# DC_DC_5V.net
KiCad netlist of a schematic drawn in Altium Designer
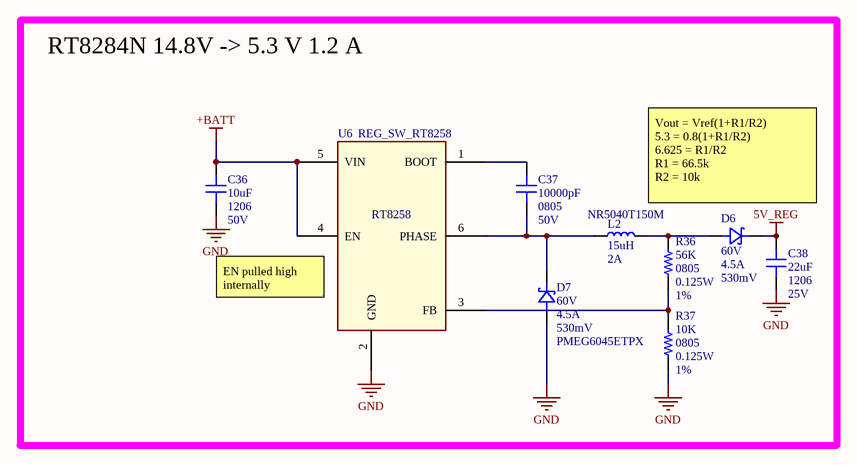
[diagram p0: DC_DC_5V.SchDoc]

(export (version "E")
  (design (tool "Eeschema 10.0.6"))
  (components
    (comp (ref "C36")
      (value "10uF")
      (footprint "CAP_1206")
      (description "CAP CER 10uF 50V 1206")
      (fields
        (field (name "PART NUMBER") "GRT31CR61H106ME01L‎")
        (field (name "PACKAGE") "1206")
        (field (name "VOLTAGE") "50V")
        (field (name "Comment") "CAP_GRT31CR61H106ME01L‎")
      )
      (libsource (lib "SecureBot") (part "CAP_GRT31CR61H106ME01L‎"))
    )
    (comp (ref "C37")
      (value "10000pF")
      (footprint "CAP_0805")
      (description "CAP CER 10000pF 50V 0805")
      (fields
        (field (name "PART NUMBER") "‎CL21B103KBANNNC")
        (field (name "PACKAGE") "0805")
        (field (name "VOLTAGE") "50V")
        (field (name "Comment") "CAP_‎‎‎‎CL21B103KBANNNC")
      )
      (libsource (lib "SecureBot") (part "CAP_‎‎‎‎CL21B103KBANNNC"))
    )
    (comp (ref "C38")
      (value "22uF")
      (footprint "CAP_1206")
      (description "CAP CER 22uF 25V 1206")
      (fields
        (field (name "PART NUMBER") "CL31A226KAHNNNE‎")
        (field (name "PACKAGE") "1206")
        (field (name "VOLTAGE") "25V")
        (field (name "Comment") "CAP_‎‎CL31A226KAHNNNE‎")
      )
      (libsource (lib "SecureBot") (part "CAP_‎‎CL31A226KAHNNNE‎"))
    )
    (comp (ref "D6")
      (value "DIODE_SCH_PMEG6045ETPX")
      (footprint "DO-214AC_SOD128")
      (description "Diode Schottky 60V 4.5A Surface Mount CFP5")
      (fields
        (field (name "VOLTAGE") "60V")
        (field (name "CURRENT") "4.5A")
        (field (name "VF") "530mV")
        (field (name "PART NUMBER") "PMEG6045ETPX")
      )
      (libsource (lib "SecureBot") (part "DIODE_SCH_PMEG6045ETPX"))
    )
    (comp (ref "D7")
      (value "DIODE_SCH_PMEG6045ETPX")
      (footprint "DO-214AC_SOD128")
      (description "Diode Schottky 60V 4.5A Surface Mount CFP5")
      (fields
        (field (name "VOLTAGE") "60V")
        (field (name "CURRENT") "4.5A")
        (field (name "VF") "530mV")
        (field (name "PART NUMBER") "PMEG6045ETPX")
      )
      (libsource (lib "SecureBot") (part "DIODE_SCH_PMEG6045ETPX"))
    )
    (comp (ref "L2")
      (value "15uH")
      (footprint "NR5040T150M")
      (description "15µH Shielded Wirewound Inductor 1.8A 104mOhm Max Nonstandard")
      (fields
        (field (name "CURRENT") "2A")
        (field (name "PART NUMBER") "NR5040T150M")
        (field (name "Comment") "IND_NR5040T150M")
      )
      (libsource (lib "SecureBot") (part "IND_NR5040T150M"))
    )
    (comp (ref "R36")
      (value "56K")
      (footprint "RES_0805")
      (description "RES 56K 1% 1/8W 0805")
      (fields
        (field (name "PART NUMBER") "‎RC0805FR-0756KL")
        (field (name "PACKAGE") "0805")
        (field (name "POWER") "0.125W")
        (field (name "TOLERANCE") "1%")
        (field (name "Comment") "RES_‎‎‎‎RC0805FR-0756KL")
      )
      (libsource (lib "SecureBot") (part "RES_‎‎‎‎RC0805FR-0756KL"))
    )
    (comp (ref "R37")
      (value "10K")
      (footprint "RES_0805")
      (description "RES 10K 1% 1/8W 0805")
      (fields
        (field (name "PART NUMBER") "‎RMCF0805FT10K0‎")
        (field (name "PACKAGE") "0805")
        (field (name "POWER") "0.125W")
        (field (name "TOLERANCE") "1%")
        (field (name "Comment") "RES_‎‎‎‎‎RMCF0805FT10K0‎")
      )
      (libsource (lib "SecureBot") (part "RES_‎‎‎‎‎RMCF0805FT10K0‎"))
    )
    (comp (ref "U6")
      (value "REG_SW_RT8258")
      (footprint "SOT23-6")
      (description "REG 1.2A, 24V, 700kHz Step-Down Converter")
      (fields (field (name "PART NUMBER") "RT8258"))
      (libsource (lib "SecureBot") (part "REG_SW_RT8258"))
    )
  )
  (nets
    (net (code "1") (name "+BATT") (class "Default")
      (node (ref "C36") (pin "1") (pinfunction "1_1") (pintype "passive"))
      (node (ref "U6") (pin "4") (pinfunction "EN_4") (pintype "passive"))
      (node (ref "U6") (pin "5") (pinfunction "VIN_5") (pintype "passive"))
    )
    (net (code "2") (name "5V_REG") (class "Default")
      (node (ref "C38") (pin "1") (pinfunction "1_1") (pintype "passive"))
      (node (ref "D6") (pin "2") (pinfunction "2_2") (pintype "passive"))
    )
    (net (code "3") (name "GND") (class "Default")
      (node (ref "C36") (pin "2") (pinfunction "2_2") (pintype "passive"))
      (node (ref "C38") (pin "2") (pinfunction "2_2") (pintype "passive"))
      (node (ref "D7") (pin "1") (pinfunction "1_1") (pintype "passive"))
      (node (ref "R37") (pin "2") (pinfunction "2_2") (pintype "passive"))
      (node (ref "U6") (pin "2") (pinfunction "GND_2") (pintype "passive"))
    )
    (net (code "4") (name "Net-(D6-Pad1)") (class "Default")
      (node (ref "D6") (pin "1") (pinfunction "1_1") (pintype "passive"))
      (node (ref "L2") (pin "2") (pinfunction "2_2") (pintype "passive"))
      (node (ref "R36") (pin "1") (pinfunction "1_1") (pintype "passive"))
    )
    (net (code "5") (name "Net-(U6-BOOT)") (class "Default")
      (node (ref "C37") (pin "1") (pinfunction "1_1") (pintype "passive"))
      (node (ref "U6") (pin "1") (pinfunction "BOOT_1") (pintype "passive"))
    )
    (net (code "6") (name "Net-(U6-FB)") (class "Default")
      (node (ref "R36") (pin "2") (pinfunction "2_2") (pintype "passive"))
      (node (ref "R37") (pin "1") (pinfunction "1_1") (pintype "passive"))
      (node (ref "U6") (pin "3") (pinfunction "FB_3") (pintype "passive"))
    )
    (net (code "7") (name "Net-(U6-PHASE)") (class "Default")
      (node (ref "C37") (pin "2") (pinfunction "2_2") (pintype "passive"))
      (node (ref "D7") (pin "2") (pinfunction "2_2") (pintype "passive"))
      (node (ref "L2") (pin "1") (pinfunction "1_1") (pintype "passive"))
      (node (ref "U6") (pin "6") (pinfunction "PHASE_6") (pintype "passive"))
    )
  )
)
